# header_conn.net
KiCad netlist of a schematic drawn in Altium Designer
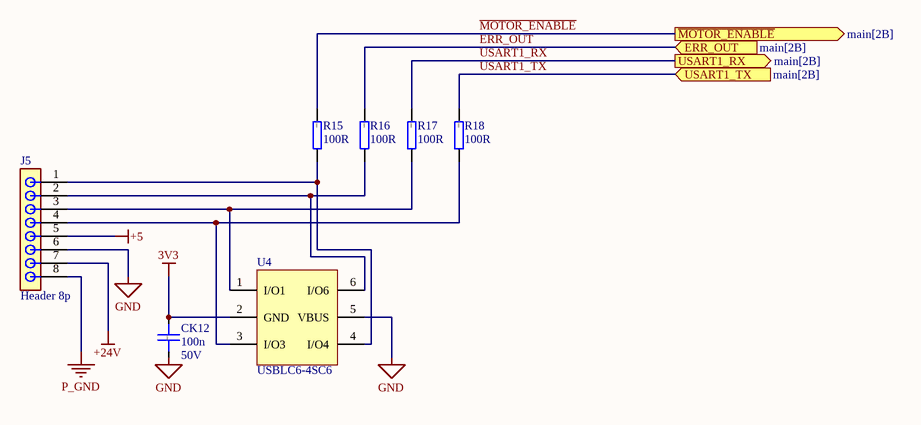
[diagram p0: header_conn.SchDoc]

(export (version "E")
  (design (tool "Eeschema 10.0.6"))
  (components
    (comp (ref "CK12")
      (value "100n")
      (footprint "CAP0603")
      (description "50V 100nF X7R ±10% 0603 Multilayer Ceramic Capacitors MLCC - SMD/SMT ROHS")
      (fields (field (name "JLCPCB PART") "C14663") (field (name "VOLTAGE RATING") "50V"))
      (libsource (lib "Kubikova ultra knihovna") (part "Cap 100n 0603"))
    )
    (comp (ref "J5")
      (value "Header 8p")
      (footprint "Pin header 8p")
      (fields
        (field (name "MANUFACTURER_PART_NUMBER") "DS1021-1*2SF11-B")
        (field (name "JLCPCB PART") "C37208")
      )
      (libsource (lib "Kubikova ultra knihovna") (part "Pin header 8p"))
    )
    (comp (ref "R15")
      (value "100R")
      (footprint "RESC2012X06N(SMR0805)")
      (description "125mW Thick Film Resistors 150V ±100ppm/℃ ±1% 100Ω 0805 Chip Resistor - Surface Mount ROHS")
      (fields (field (name "JLCPCB PART") "C17408") (field (name "AUTHOR") "JP/27.03.2014"))
      (libsource (lib "Kubikova ultra knihovna") (part "Res 100R 0805"))
    )
    (comp (ref "R16")
      (value "100R")
      (footprint "RESC2012X06N(SMR0805)")
      (description "125mW Thick Film Resistors 150V ±100ppm/℃ ±1% 100Ω 0805 Chip Resistor - Surface Mount ROHS")
      (fields (field (name "JLCPCB PART") "C17408") (field (name "AUTHOR") "JP/27.03.2014"))
      (libsource (lib "Kubikova ultra knihovna") (part "Res 100R 0805"))
    )
    (comp (ref "R17")
      (value "100R")
      (footprint "RESC2012X06N(SMR0805)")
      (description "125mW Thick Film Resistors 150V ±100ppm/℃ ±1% 100Ω 0805 Chip Resistor - Surface Mount ROHS")
      (fields (field (name "JLCPCB PART") "C17408") (field (name "AUTHOR") "JP/27.03.2014"))
      (libsource (lib "Kubikova ultra knihovna") (part "Res 100R 0805"))
    )
    (comp (ref "R18")
      (value "100R")
      (footprint "RESC2012X06N(SMR0805)")
      (description "125mW Thick Film Resistors 150V ±100ppm/℃ ±1% 100Ω 0805 Chip Resistor - Surface Mount ROHS")
      (fields (field (name "JLCPCB PART") "C17408") (field (name "AUTHOR") "JP/27.03.2014"))
      (libsource (lib "Kubikova ultra knihovna") (part "Res 100R 0805"))
    )
    (comp (ref "U4")
      (value "USBLC6-4SC6")
      (footprint "SOT23-6")
      (description "5A 17V 6V Unidirectional 5.25V SOT-23-6 ESD and Surge Protection (TVS/ESD) ROHS")
      (fields (field (name "JLCPCB PART") "C111212"))
      (libsource (lib "Kubikova ultra knihovna") (part "USBLC6-4SC6"))
    )
  )
  (nets
    (net (code "1") (name "+5") (class "Default")
      (node (ref "J5") (pin "5") (pinfunction "5_5") (pintype "passive"))
    )
    (net (code "2") (name "+24V") (class "Default")
      (node (ref "J5") (pin "7") (pinfunction "7_7") (pintype "passive"))
    )
    (net (code "3") (name "/ERR_OUT") (class "Default")
      (node (ref "R16") (pin "2") (pinfunction "2_2") (pintype "passive"))
    )
    (net (code "4") (name "/USART1_RX") (class "Default")
      (node (ref "R17") (pin "2") (pinfunction "2_2") (pintype "passive"))
    )
    (net (code "5") (name "/USART1_TX") (class "Default")
      (node (ref "R18") (pin "2") (pinfunction "2_2") (pintype "passive"))
    )
    (net (code "6") (name "/~{MOTOR_ENABLE}") (class "Default")
      (node (ref "R15") (pin "2") (pinfunction "2_2") (pintype "passive"))
    )
    (net (code "7") (name "3V3") (class "Default")
      (node (ref "CK12") (pin "1") (pinfunction "1_1") (pintype "passive"))
      (node (ref "U4") (pin "2") (pinfunction "GND_2") (pintype "passive"))
    )
    (net (code "8") (name "GND") (class "Default")
      (node (ref "CK12") (pin "2") (pinfunction "2_2") (pintype "passive"))
      (node (ref "J5") (pin "6") (pinfunction "6_6") (pintype "passive"))
      (node (ref "U4") (pin "5") (pinfunction "VBUS_5") (pintype "passive"))
    )
    (net (code "9") (name "Net-(U4-I{slash}O1)") (class "Default")
      (node (ref "J5") (pin "3") (pinfunction "3_3") (pintype "passive"))
      (node (ref "R17") (pin "1") (pinfunction "1_1") (pintype "passive"))
      (node (ref "U4") (pin "1") (pinfunction "I/O1_1") (pintype "passive"))
    )
    (net (code "10") (name "Net-(U4-I{slash}O3)") (class "Default")
      (node (ref "J5") (pin "4") (pinfunction "4_4") (pintype "passive"))
      (node (ref "R18") (pin "1") (pinfunction "1_1") (pintype "passive"))
      (node (ref "U4") (pin "3") (pinfunction "I/O3_3") (pintype "passive"))
    )
    (net (code "11") (name "Net-(U4-I{slash}O4)") (class "Default")
      (node (ref "J5") (pin "1") (pinfunction "1_1") (pintype "passive"))
      (node (ref "R15") (pin "1") (pinfunction "1_1") (pintype "passive"))
      (node (ref "U4") (pin "4") (pinfunction "I/O4_4") (pintype "passive"))
    )
    (net (code "12") (name "Net-(U4-I{slash}O6)") (class "Default")
      (node (ref "J5") (pin "2") (pinfunction "2_2") (pintype "passive"))
      (node (ref "R16") (pin "1") (pinfunction "1_1") (pintype "passive"))
      (node (ref "U4") (pin "6") (pinfunction "I/O6_6") (pintype "passive"))
    )
    (net (code "13") (name "P_GND") (class "Default")
      (node (ref "J5") (pin "8") (pinfunction "8_8") (pintype "passive"))
    )
  )
)
